# SENSORS_SMALL_SCH.net
KiCad netlist of a schematic drawn in Altium Designer
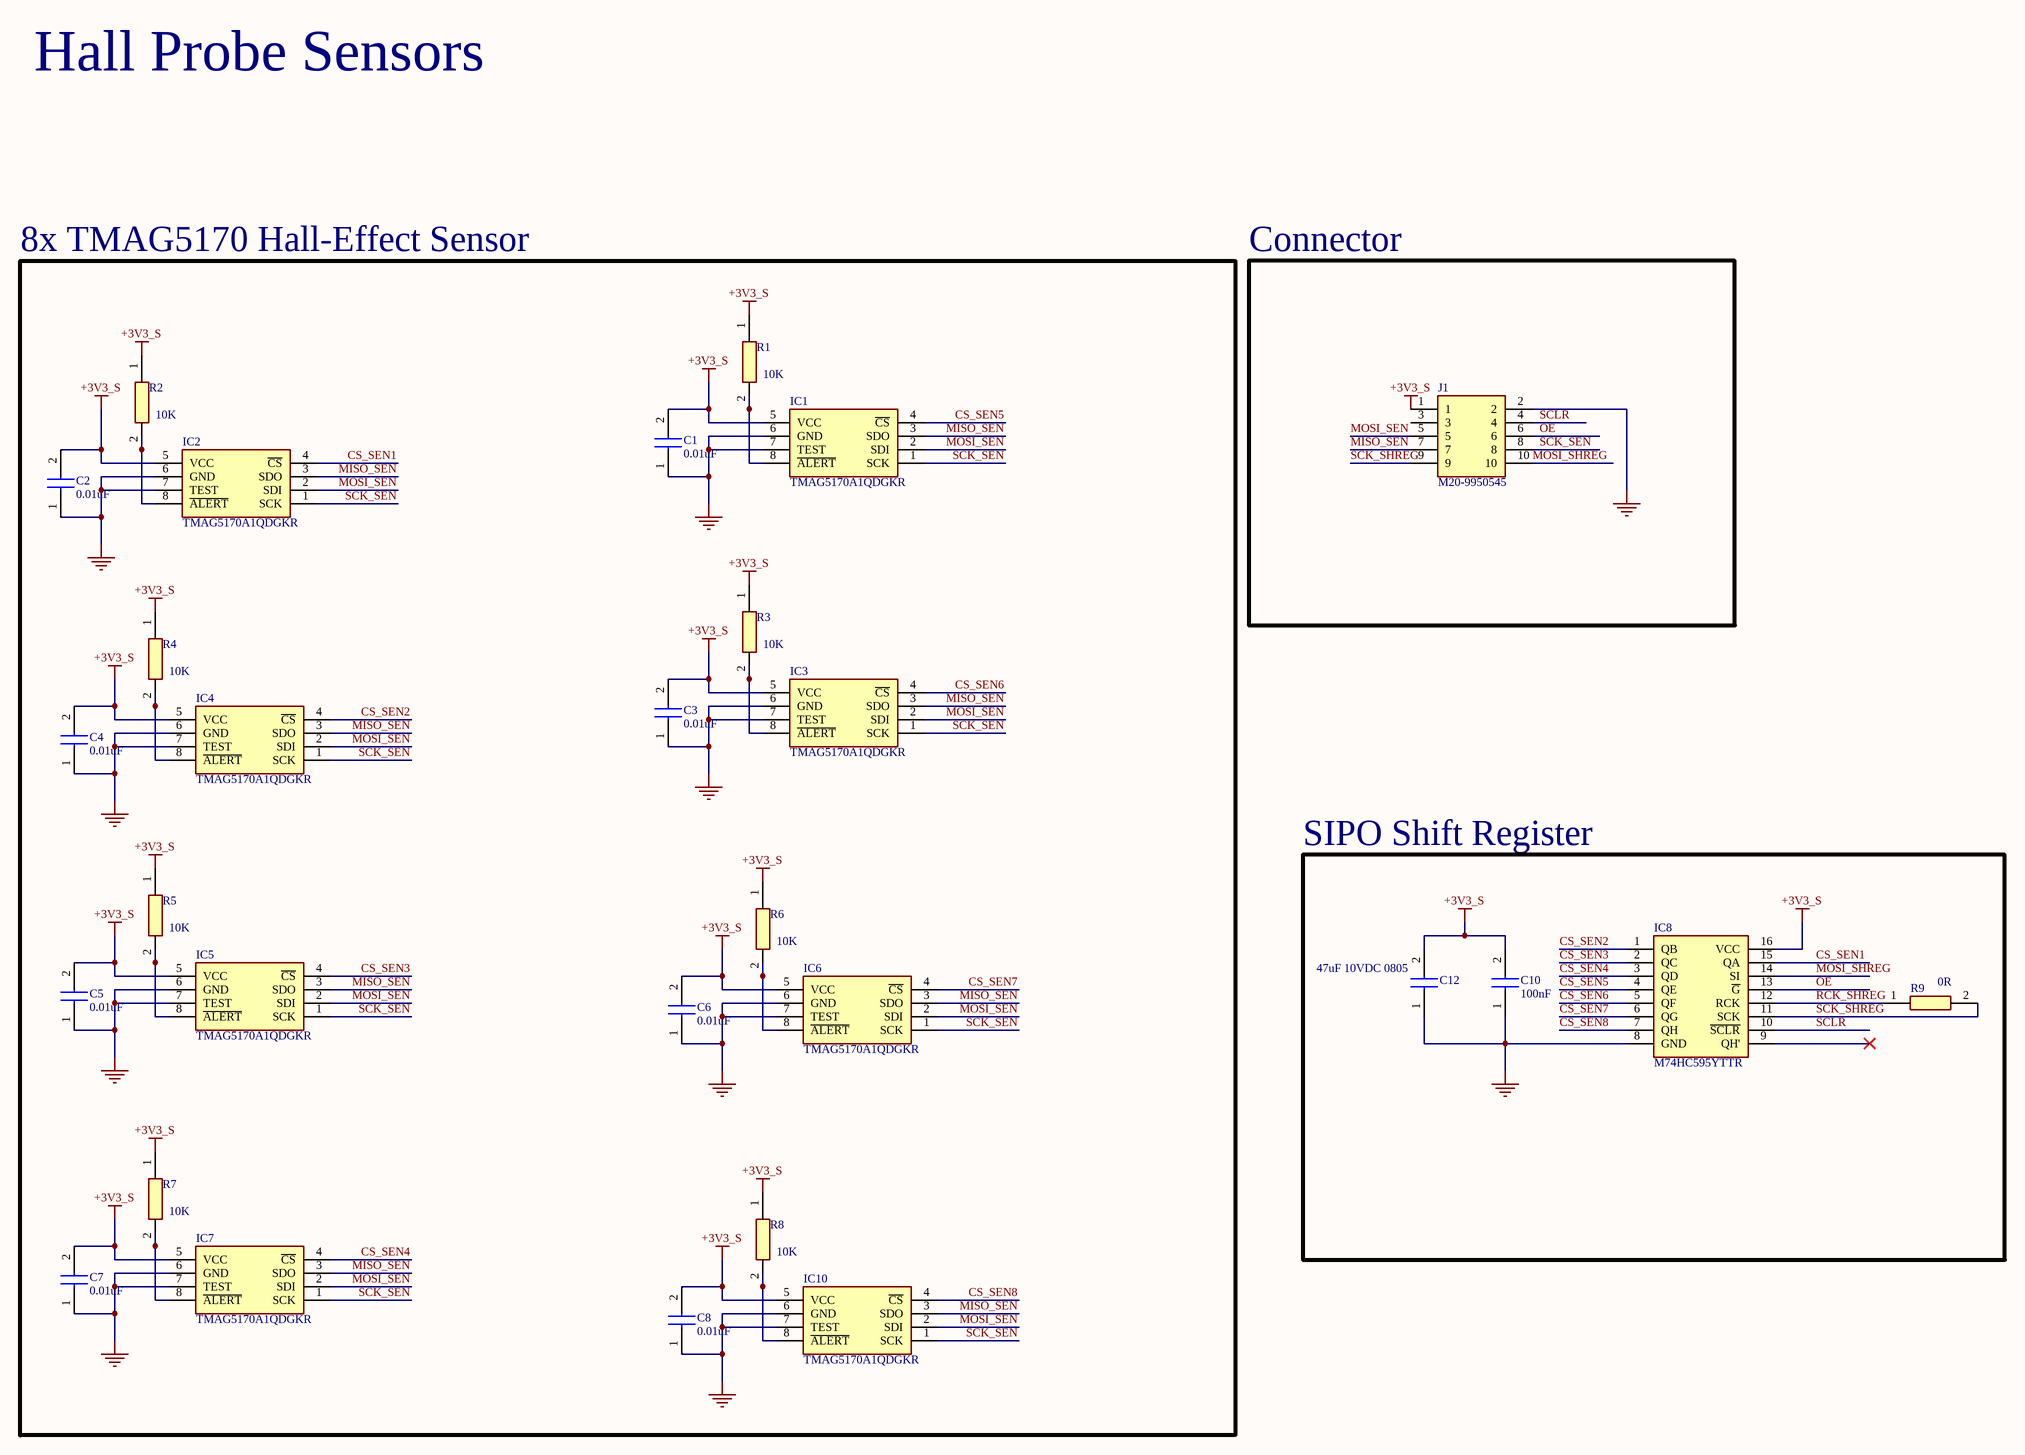
[diagram p0: SENSORS_SMALL_SCH.SchDoc]

(export (version "E")
  (design (tool "Eeschema 10.0.6"))
  (components
    (comp (ref "C1")
      (value "0.01uF")
      (footprint "SamacSys:C0603")
      (description "Capacitor")
      (fields
        (field (name "MANUFACTURER_PART_NUMBER") "C0603C103J4RACTU")
        (field (name "MOUSER PART NUMBER") "80-C0603C103J4R")
      )
      (libsource (lib "*") (part "C0603C103J4RACTU"))
    )
    (comp (ref "C2")
      (value "0.01uF")
      (footprint "SamacSys:C0603")
      (description "Capacitor")
      (fields
        (field (name "MANUFACTURER_PART_NUMBER") "C0603C103J4RACTU")
        (field (name "MOUSER PART NUMBER") "80-C0603C103J4R")
      )
      (libsource (lib "*") (part "C0603C103J4RACTU"))
    )
    (comp (ref "C3")
      (value "0.01uF")
      (footprint "SamacSys:C0603")
      (description "Capacitor")
      (fields
        (field (name "MANUFACTURER_PART_NUMBER") "C0603C103J4RACTU")
        (field (name "MOUSER PART NUMBER") "80-C0603C103J4R")
      )
      (libsource (lib "*") (part "C0603C103J4RACTU"))
    )
    (comp (ref "C4")
      (value "0.01uF")
      (footprint "SamacSys:C0603")
      (description "Capacitor")
      (fields
        (field (name "MANUFACTURER_PART_NUMBER") "C0603C103J4RACTU")
        (field (name "MOUSER PART NUMBER") "80-C0603C103J4R")
      )
      (libsource (lib "*") (part "C0603C103J4RACTU"))
    )
    (comp (ref "C5")
      (value "0.01uF")
      (footprint "SamacSys:C0603")
      (description "Capacitor")
      (fields
        (field (name "MANUFACTURER_PART_NUMBER") "C0603C103J4RACTU")
        (field (name "MOUSER PART NUMBER") "80-C0603C103J4R")
      )
      (libsource (lib "*") (part "C0603C103J4RACTU"))
    )
    (comp (ref "C6")
      (value "0.01uF")
      (footprint "SamacSys:C0603")
      (description "Capacitor")
      (fields
        (field (name "MANUFACTURER_PART_NUMBER") "C0603C103J4RACTU")
        (field (name "MOUSER PART NUMBER") "80-C0603C103J4R")
      )
      (libsource (lib "*") (part "C0603C103J4RACTU"))
    )
    (comp (ref "C7")
      (value "0.01uF")
      (footprint "SamacSys:C0603")
      (description "Capacitor")
      (fields
        (field (name "MANUFACTURER_PART_NUMBER") "C0603C103J4RACTU")
        (field (name "MOUSER PART NUMBER") "80-C0603C103J4R")
      )
      (libsource (lib "*") (part "C0603C103J4RACTU"))
    )
    (comp (ref "C8")
      (value "0.01uF")
      (footprint "SamacSys:C0603")
      (description "Capacitor")
      (fields
        (field (name "MANUFACTURER_PART_NUMBER") "C0603C103J4RACTU")
        (field (name "MOUSER PART NUMBER") "80-C0603C103J4R")
      )
      (libsource (lib "*") (part "C0603C103J4RACTU"))
    )
    (comp (ref "C10")
      (value "100nF")
      (footprint "SamacSys:CAPC1608X95N")
      (description "Capacitor")
      (fields
        (field (name "MANUFACTURER_PART_NUMBER") "C0603C104J4RAC")
        (field (name "MOUSER PART NUMBER") "80-C0603C104J4RAC")
      )
      (libsource (lib "SamacSys") (part "C0603C104J4RAC"))
    )
    (comp (ref "C12")
      (value "47uF 10VDC 0805")
      (footprint "SamacSys:CAPC2012X145N")
      (description "Capacitor")
      (fields
        (field (name "MANUFACTURER_PART_NUMBER") "GRM21BR61A476ME15K")
        (field (name "MOUSER PART NUMBER") "81-GRM21BR61A476ME5K")
      )
      (libsource (lib "*") (part "GRM21BR61A476ME15K"))
    )
    (comp (ref "IC1")
      (value "TMAG5170A1QDGKR")
      (footprint "SamacSys:SOP65P490X110-8N")
      (description "Integrated Circuit")
      (fields (field (name "MOUSER PART NUMBER") "595-TMAG5170A1QDGKR"))
      (libsource (lib "*") (part "TMAG5170A1QDGKR"))
    )
    (comp (ref "IC2")
      (value "TMAG5170A1QDGKR")
      (footprint "SamacSys:SOP65P490X110-8N")
      (description "Integrated Circuit")
      (fields (field (name "MOUSER PART NUMBER") "595-TMAG5170A1QDGKR"))
      (libsource (lib "*") (part "TMAG5170A1QDGKR"))
    )
    (comp (ref "IC3")
      (value "TMAG5170A1QDGKR")
      (footprint "SamacSys:SOP65P490X110-8N")
      (description "Integrated Circuit")
      (fields (field (name "MOUSER PART NUMBER") "595-TMAG5170A1QDGKR"))
      (libsource (lib "*") (part "TMAG5170A1QDGKR"))
    )
    (comp (ref "IC4")
      (value "TMAG5170A1QDGKR")
      (footprint "SamacSys:SOP65P490X110-8N")
      (description "Integrated Circuit")
      (fields (field (name "MOUSER PART NUMBER") "595-TMAG5170A1QDGKR"))
      (libsource (lib "*") (part "TMAG5170A1QDGKR"))
    )
    (comp (ref "IC5")
      (value "TMAG5170A1QDGKR")
      (footprint "SamacSys:SOP65P490X110-8N")
      (description "Integrated Circuit")
      (fields (field (name "MOUSER PART NUMBER") "595-TMAG5170A1QDGKR"))
      (libsource (lib "*") (part "TMAG5170A1QDGKR"))
    )
    (comp (ref "IC6")
      (value "TMAG5170A1QDGKR")
      (footprint "SamacSys:SOP65P490X110-8N")
      (description "Integrated Circuit")
      (fields (field (name "MOUSER PART NUMBER") "595-TMAG5170A1QDGKR"))
      (libsource (lib "*") (part "TMAG5170A1QDGKR"))
    )
    (comp (ref "IC7")
      (value "TMAG5170A1QDGKR")
      (footprint "SamacSys:SOP65P490X110-8N")
      (description "Integrated Circuit")
      (fields (field (name "MOUSER PART NUMBER") "595-TMAG5170A1QDGKR"))
      (libsource (lib "*") (part "TMAG5170A1QDGKR"))
    )
    (comp (ref "IC8")
      (value "M74HC595YTTR")
      (footprint "SamacSys:SOP65P640X120-16N")
      (description "Integrated Circuit")
      (fields (field (name "MOUSER PART NUMBER") "511-M74HC595YTTR"))
      (libsource (lib "*") (part "M74HC595YTTR"))
    )
    (comp (ref "IC10")
      (value "TMAG5170A1QDGKR")
      (footprint "SamacSys:SOP65P490X110-8N")
      (description "Integrated Circuit")
      (fields (field (name "MOUSER PART NUMBER") "595-TMAG5170A1QDGKR"))
      (libsource (lib "*") (part "TMAG5170A1QDGKR"))
    )
    (comp (ref "J1")
      (value "M20-9950545")
      (footprint "SamacSys:HDRRA10W66P254_2X5_1270X254X528P")
      (description "Connector")
      (fields (field (name "MOUSER PART NUMBER") "855-M20-9950545"))
      (libsource (lib "SamacSys") (part "M20-9950545"))
    )
    (comp (ref "R1")
      (value "10K")
      (footprint "SamacSys:RESC1608X55N")
      (description "Resistor")
      (fields
        (field (name "MANUFACTURER_PART_NUMBER") "RK73B1JTTD103J")
        (field (name "MOUSER PART NUMBER") "660-RK73B1JTTD103J")
      )
      (libsource (lib "*") (part "RK73B1JTTD103J"))
    )
    (comp (ref "R2")
      (value "10K")
      (footprint "SamacSys:RESC1608X55N")
      (description "Resistor")
      (fields
        (field (name "MANUFACTURER_PART_NUMBER") "RK73B1JTTD103J")
        (field (name "MOUSER PART NUMBER") "660-RK73B1JTTD103J")
      )
      (libsource (lib "*") (part "RK73B1JTTD103J"))
    )
    (comp (ref "R3")
      (value "10K")
      (footprint "SamacSys:RESC1608X55N")
      (description "Resistor")
      (fields
        (field (name "MANUFACTURER_PART_NUMBER") "RK73B1JTTD103J")
        (field (name "MOUSER PART NUMBER") "660-RK73B1JTTD103J")
      )
      (libsource (lib "*") (part "RK73B1JTTD103J"))
    )
    (comp (ref "R4")
      (value "10K")
      (footprint "SamacSys:RESC1608X55N")
      (description "Resistor")
      (fields
        (field (name "MANUFACTURER_PART_NUMBER") "RK73B1JTTD103J")
        (field (name "MOUSER PART NUMBER") "660-RK73B1JTTD103J")
      )
      (libsource (lib "*") (part "RK73B1JTTD103J"))
    )
    (comp (ref "R5")
      (value "10K")
      (footprint "SamacSys:RESC1608X55N")
      (description "Resistor")
      (fields
        (field (name "MANUFACTURER_PART_NUMBER") "RK73B1JTTD103J")
        (field (name "MOUSER PART NUMBER") "660-RK73B1JTTD103J")
      )
      (libsource (lib "*") (part "RK73B1JTTD103J"))
    )
    (comp (ref "R6")
      (value "10K")
      (footprint "SamacSys:RESC1608X55N")
      (description "Resistor")
      (fields
        (field (name "MANUFACTURER_PART_NUMBER") "RK73B1JTTD103J")
        (field (name "MOUSER PART NUMBER") "660-RK73B1JTTD103J")
      )
      (libsource (lib "*") (part "RK73B1JTTD103J"))
    )
    (comp (ref "R7")
      (value "10K")
      (footprint "SamacSys:RESC1608X55N")
      (description "Resistor")
      (fields
        (field (name "MANUFACTURER_PART_NUMBER") "RK73B1JTTD103J")
        (field (name "MOUSER PART NUMBER") "660-RK73B1JTTD103J")
      )
      (libsource (lib "*") (part "RK73B1JTTD103J"))
    )
    (comp (ref "R8")
      (value "10K")
      (footprint "SamacSys:RESC1608X55N")
      (description "Resistor")
      (fields
        (field (name "MANUFACTURER_PART_NUMBER") "RK73B1JTTD103J")
        (field (name "MOUSER PART NUMBER") "660-RK73B1JTTD103J")
      )
      (libsource (lib "*") (part "RK73B1JTTD103J"))
    )
    (comp (ref "R9")
      (value "0R")
      (footprint "SamacSys:RESC1608X55N")
      (description "Resistor")
      (fields
        (field (name "MANUFACTURER_PART_NUMBER") "RK73B1JTTD103J")
        (field (name "MOUSER PART NUMBER") "660-RK73B1JTTD103J")
      )
      (libsource (lib "") (part "RK73B1JTTD103J_1"))
    )
  )
  (nets
    (net (code "1") (name "+3V3_S") (class "Default")
      (node (ref "C1") (pin "2") (pinfunction "2_2") (pintype "passive"))
      (node (ref "C10") (pin "2") (pinfunction "2_2") (pintype "passive"))
      (node (ref "C12") (pin "2") (pinfunction "2_2") (pintype "passive"))
      (node (ref "C2") (pin "2") (pinfunction "2_2") (pintype "passive"))
      (node (ref "C3") (pin "2") (pinfunction "2_2") (pintype "passive"))
      (node (ref "C4") (pin "2") (pinfunction "2_2") (pintype "passive"))
      (node (ref "C5") (pin "2") (pinfunction "2_2") (pintype "passive"))
      (node (ref "C6") (pin "2") (pinfunction "2_2") (pintype "passive"))
      (node (ref "C7") (pin "2") (pinfunction "2_2") (pintype "passive"))
      (node (ref "C8") (pin "2") (pinfunction "2_2") (pintype "passive"))
      (node (ref "IC1") (pin "5") (pinfunction "VCC_5") (pintype "passive"))
      (node (ref "IC10") (pin "5") (pinfunction "VCC_5") (pintype "passive"))
      (node (ref "IC2") (pin "5") (pinfunction "VCC_5") (pintype "passive"))
      (node (ref "IC3") (pin "5") (pinfunction "VCC_5") (pintype "passive"))
      (node (ref "IC4") (pin "5") (pinfunction "VCC_5") (pintype "passive"))
      (node (ref "IC5") (pin "5") (pinfunction "VCC_5") (pintype "passive"))
      (node (ref "IC6") (pin "5") (pinfunction "VCC_5") (pintype "passive"))
      (node (ref "IC7") (pin "5") (pinfunction "VCC_5") (pintype "passive"))
      (node (ref "IC8") (pin "16") (pinfunction "VCC_16") (pintype "passive"))
      (node (ref "J1") (pin "1") (pinfunction "1_1") (pintype "passive"))
      (node (ref "R1") (pin "1") (pinfunction "1_1") (pintype "passive"))
      (node (ref "R2") (pin "1") (pinfunction "1_1") (pintype "passive"))
      (node (ref "R3") (pin "1") (pinfunction "1_1") (pintype "passive"))
      (node (ref "R4") (pin "1") (pinfunction "1_1") (pintype "passive"))
      (node (ref "R5") (pin "1") (pinfunction "1_1") (pintype "passive"))
      (node (ref "R6") (pin "1") (pinfunction "1_1") (pintype "passive"))
      (node (ref "R7") (pin "1") (pinfunction "1_1") (pintype "passive"))
      (node (ref "R8") (pin "1") (pinfunction "1_1") (pintype "passive"))
    )
    (net (code "3") (name "/CS_SEN1") (class "Default")
      (node (ref "IC2") (pin "4") (pinfunction "~{CS}_4") (pintype "passive"))
      (node (ref "IC8") (pin "15") (pinfunction "QA_15") (pintype "passive"))
    )
    (net (code "4") (name "/CS_SEN2") (class "Default")
      (node (ref "IC4") (pin "4") (pinfunction "~{CS}_4") (pintype "passive"))
      (node (ref "IC8") (pin "1") (pinfunction "QB_1") (pintype "passive"))
    )
    (net (code "5") (name "/CS_SEN3") (class "Default")
      (node (ref "IC5") (pin "4") (pinfunction "~{CS}_4") (pintype "passive"))
      (node (ref "IC8") (pin "2") (pinfunction "QC_2") (pintype "passive"))
    )
    (net (code "6") (name "/CS_SEN4") (class "Default")
      (node (ref "IC7") (pin "4") (pinfunction "~{CS}_4") (pintype "passive"))
      (node (ref "IC8") (pin "3") (pinfunction "QD_3") (pintype "passive"))
    )
    (net (code "7") (name "/CS_SEN5") (class "Default")
      (node (ref "IC1") (pin "4") (pinfunction "~{CS}_4") (pintype "passive"))
      (node (ref "IC8") (pin "4") (pinfunction "QE_4") (pintype "passive"))
    )
    (net (code "8") (name "/CS_SEN6") (class "Default")
      (node (ref "IC3") (pin "4") (pinfunction "~{CS}_4") (pintype "passive"))
      (node (ref "IC8") (pin "5") (pinfunction "QF_5") (pintype "passive"))
    )
    (net (code "9") (name "/CS_SEN7") (class "Default")
      (node (ref "IC6") (pin "4") (pinfunction "~{CS}_4") (pintype "passive"))
      (node (ref "IC8") (pin "6") (pinfunction "QG_6") (pintype "passive"))
    )
    (net (code "10") (name "/CS_SEN8") (class "Default")
      (node (ref "IC10") (pin "4") (pinfunction "~{CS}_4") (pintype "passive"))
      (node (ref "IC8") (pin "7") (pinfunction "QH_7") (pintype "passive"))
    )
    (net (code "11") (name "/MISO_SEN") (class "Default")
      (node (ref "IC1") (pin "3") (pinfunction "SDO_3") (pintype "passive"))
      (node (ref "IC10") (pin "3") (pinfunction "SDO_3") (pintype "passive"))
      (node (ref "IC2") (pin "3") (pinfunction "SDO_3") (pintype "passive"))
      (node (ref "IC3") (pin "3") (pinfunction "SDO_3") (pintype "passive"))
      (node (ref "IC4") (pin "3") (pinfunction "SDO_3") (pintype "passive"))
      (node (ref "IC5") (pin "3") (pinfunction "SDO_3") (pintype "passive"))
      (node (ref "IC6") (pin "3") (pinfunction "SDO_3") (pintype "passive"))
      (node (ref "IC7") (pin "3") (pinfunction "SDO_3") (pintype "passive"))
      (node (ref "J1") (pin "7") (pinfunction "7_7") (pintype "passive"))
    )
    (net (code "12") (name "/MOSI_SEN") (class "Default")
      (node (ref "IC1") (pin "2") (pinfunction "SDI_2") (pintype "passive"))
      (node (ref "IC10") (pin "2") (pinfunction "SDI_2") (pintype "passive"))
      (node (ref "IC2") (pin "2") (pinfunction "SDI_2") (pintype "passive"))
      (node (ref "IC3") (pin "2") (pinfunction "SDI_2") (pintype "passive"))
      (node (ref "IC4") (pin "2") (pinfunction "SDI_2") (pintype "passive"))
      (node (ref "IC5") (pin "2") (pinfunction "SDI_2") (pintype "passive"))
      (node (ref "IC6") (pin "2") (pinfunction "SDI_2") (pintype "passive"))
      (node (ref "IC7") (pin "2") (pinfunction "SDI_2") (pintype "passive"))
      (node (ref "J1") (pin "5") (pinfunction "5_5") (pintype "passive"))
    )
    (net (code "13") (name "/MOSI_SHREG") (class "Default")
      (node (ref "IC8") (pin "14") (pinfunction "SI_14") (pintype "passive"))
      (node (ref "J1") (pin "10") (pinfunction "10_10") (pintype "passive"))
    )
    (net (code "14") (name "/OE") (class "Default")
      (node (ref "IC8") (pin "13") (pinfunction "~{G}_13") (pintype "passive"))
      (node (ref "J1") (pin "6") (pinfunction "6_6") (pintype "passive"))
    )
    (net (code "15") (name "/RCK_SHREG") (class "Default")
      (node (ref "IC8") (pin "12") (pinfunction "RCK_12") (pintype "passive"))
      (node (ref "R9") (pin "1") (pinfunction "1_1") (pintype "passive"))
    )
    (net (code "16") (name "/SCK_SEN") (class "Default")
      (node (ref "IC1") (pin "1") (pinfunction "SCK_1") (pintype "passive"))
      (node (ref "IC10") (pin "1") (pinfunction "SCK_1") (pintype "passive"))
      (node (ref "IC2") (pin "1") (pinfunction "SCK_1") (pintype "passive"))
      (node (ref "IC3") (pin "1") (pinfunction "SCK_1") (pintype "passive"))
      (node (ref "IC4") (pin "1") (pinfunction "SCK_1") (pintype "passive"))
      (node (ref "IC5") (pin "1") (pinfunction "SCK_1") (pintype "passive"))
      (node (ref "IC6") (pin "1") (pinfunction "SCK_1") (pintype "passive"))
      (node (ref "IC7") (pin "1") (pinfunction "SCK_1") (pintype "passive"))
      (node (ref "J1") (pin "8") (pinfunction "8_8") (pintype "passive"))
    )
    (net (code "17") (name "/SCK_SHREG") (class "Default")
      (node (ref "IC8") (pin "11") (pinfunction "SCK_11") (pintype "passive"))
      (node (ref "J1") (pin "9") (pinfunction "9_9") (pintype "passive"))
      (node (ref "R9") (pin "2") (pinfunction "2_2") (pintype "passive"))
    )
    (net (code "18") (name "/SCLR") (class "Default")
      (node (ref "IC8") (pin "10") (pinfunction "~{SCLR}_10") (pintype "passive"))
      (node (ref "J1") (pin "4") (pinfunction "4_4") (pintype "passive"))
    )
    (net (code "19") (name "GND") (class "Default")
      (node (ref "C1") (pin "1") (pinfunction "1_1") (pintype "passive"))
      (node (ref "C10") (pin "1") (pinfunction "1_1") (pintype "passive"))
      (node (ref "C12") (pin "1") (pinfunction "1_1") (pintype "passive"))
      (node (ref "C2") (pin "1") (pinfunction "1_1") (pintype "passive"))
      (node (ref "C3") (pin "1") (pinfunction "1_1") (pintype "passive"))
      (node (ref "C4") (pin "1") (pinfunction "1_1") (pintype "passive"))
      (node (ref "C5") (pin "1") (pinfunction "1_1") (pintype "passive"))
      (node (ref "C6") (pin "1") (pinfunction "1_1") (pintype "passive"))
      (node (ref "C7") (pin "1") (pinfunction "1_1") (pintype "passive"))
      (node (ref "C8") (pin "1") (pinfunction "1_1") (pintype "passive"))
      (node (ref "IC1") (pin "6") (pinfunction "GND_6") (pintype "passive"))
      (node (ref "IC1") (pin "7") (pinfunction "TEST_7") (pintype "passive"))
      (node (ref "IC10") (pin "6") (pinfunction "GND_6") (pintype "passive"))
      (node (ref "IC10") (pin "7") (pinfunction "TEST_7") (pintype "passive"))
      (node (ref "IC2") (pin "6") (pinfunction "GND_6") (pintype "passive"))
      (node (ref "IC2") (pin "7") (pinfunction "TEST_7") (pintype "passive"))
      (node (ref "IC3") (pin "6") (pinfunction "GND_6") (pintype "passive"))
      (node (ref "IC3") (pin "7") (pinfunction "TEST_7") (pintype "passive"))
      (node (ref "IC4") (pin "6") (pinfunction "GND_6") (pintype "passive"))
      (node (ref "IC4") (pin "7") (pinfunction "TEST_7") (pintype "passive"))
      (node (ref "IC5") (pin "6") (pinfunction "GND_6") (pintype "passive"))
      (node (ref "IC5") (pin "7") (pinfunction "TEST_7") (pintype "passive"))
      (node (ref "IC6") (pin "6") (pinfunction "GND_6") (pintype "passive"))
      (node (ref "IC6") (pin "7") (pinfunction "TEST_7") (pintype "passive"))
      (node (ref "IC7") (pin "6") (pinfunction "GND_6") (pintype "passive"))
      (node (ref "IC7") (pin "7") (pinfunction "TEST_7") (pintype "passive"))
      (node (ref "IC8") (pin "8") (pinfunction "GND_8") (pintype "passive"))
      (node (ref "J1") (pin "2") (pinfunction "2_2") (pintype "passive"))
    )
    (net (code "20") (name "Net-(IC1-~{ALERT})") (class "Default")
      (node (ref "IC1") (pin "8") (pinfunction "~{ALERT}_8") (pintype "passive"))
      (node (ref "R1") (pin "2") (pinfunction "2_2") (pintype "passive"))
    )
    (net (code "21") (name "Net-(IC2-~{ALERT})") (class "Default")
      (node (ref "IC2") (pin "8") (pinfunction "~{ALERT}_8") (pintype "passive"))
      (node (ref "R2") (pin "2") (pinfunction "2_2") (pintype "passive"))
    )
    (net (code "22") (name "Net-(IC3-~{ALERT})") (class "Default")
      (node (ref "IC3") (pin "8") (pinfunction "~{ALERT}_8") (pintype "passive"))
      (node (ref "R3") (pin "2") (pinfunction "2_2") (pintype "passive"))
    )
    (net (code "23") (name "Net-(IC4-~{ALERT})") (class "Default")
      (node (ref "IC4") (pin "8") (pinfunction "~{ALERT}_8") (pintype "passive"))
      (node (ref "R4") (pin "2") (pinfunction "2_2") (pintype "passive"))
    )
    (net (code "24") (name "Net-(IC5-~{ALERT})") (class "Default")
      (node (ref "IC5") (pin "8") (pinfunction "~{ALERT}_8") (pintype "passive"))
      (node (ref "R5") (pin "2") (pinfunction "2_2") (pintype "passive"))
    )
    (net (code "25") (name "Net-(IC6-~{ALERT})") (class "Default")
      (node (ref "IC6") (pin "8") (pinfunction "~{ALERT}_8") (pintype "passive"))
      (node (ref "R6") (pin "2") (pinfunction "2_2") (pintype "passive"))
    )
    (net (code "26") (name "Net-(IC7-~{ALERT})") (class "Default")
      (node (ref "IC7") (pin "8") (pinfunction "~{ALERT}_8") (pintype "passive"))
      (node (ref "R7") (pin "2") (pinfunction "2_2") (pintype "passive"))
    )
    (net (code "27") (name "Net-(IC10-~{ALERT})") (class "Default")
      (node (ref "IC10") (pin "8") (pinfunction "~{ALERT}_8") (pintype "passive"))
      (node (ref "R8") (pin "2") (pinfunction "2_2") (pintype "passive"))
    )
    (net (code "28") (name "unconnected-(IC8-QH'-Pad9)") (class "Default")
      (node (ref "IC8") (pin "9") (pinfunction "QH'_9") (pintype "passive+no_connect"))
    )
    (net (code "29") (name "unconnected-(J1-Pad3)") (class "Default")
      (node (ref "J1") (pin "3") (pinfunction "3_3") (pintype "passive"))
    )
  )
)
